# Sensor.net
KiCad netlist of a schematic drawn in Altium Designer
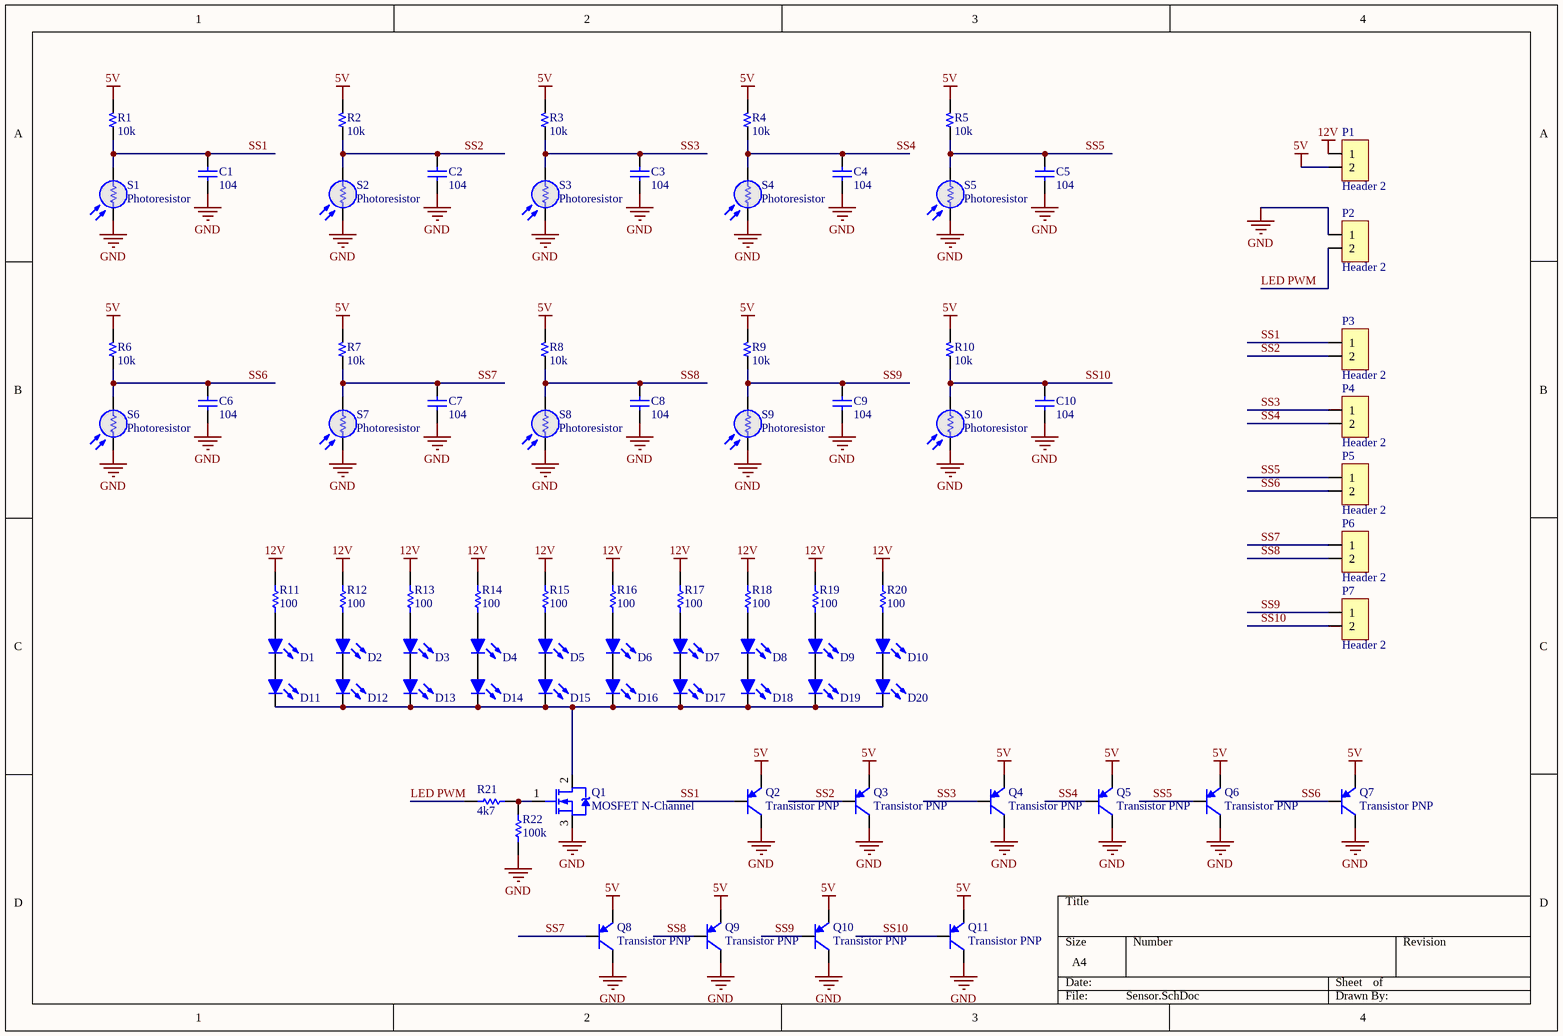
[diagram p0: Sensor.SchDoc]

(export (version "E")
  (design (tool "Eeschema 10.0.6"))
  (components
    (comp (ref "C1")
      (value "104")
      (footprint "C 0805")
      (description "Capacitor non-pol")
      (libsource (lib "chipfc_altium_libs") (part "Capacitor NP"))
    )
    (comp (ref "C2")
      (value "104")
      (footprint "C 0805")
      (description "Capacitor non-pol")
      (libsource (lib "chipfc_altium_libs") (part "Capacitor NP"))
    )
    (comp (ref "C3")
      (value "104")
      (footprint "C 0805")
      (description "Capacitor non-pol")
      (libsource (lib "chipfc_altium_libs") (part "Capacitor NP"))
    )
    (comp (ref "C4")
      (value "104")
      (footprint "C 0805")
      (description "Capacitor non-pol")
      (libsource (lib "chipfc_altium_libs") (part "Capacitor NP"))
    )
    (comp (ref "C5")
      (value "104")
      (footprint "C 0805")
      (description "Capacitor non-pol")
      (libsource (lib "chipfc_altium_libs") (part "Capacitor NP"))
    )
    (comp (ref "C6")
      (value "104")
      (footprint "C 0805")
      (description "Capacitor non-pol")
      (libsource (lib "chipfc_altium_libs") (part "Capacitor NP"))
    )
    (comp (ref "C7")
      (value "104")
      (footprint "C 0805")
      (description "Capacitor non-pol")
      (libsource (lib "chipfc_altium_libs") (part "Capacitor NP"))
    )
    (comp (ref "C8")
      (value "104")
      (footprint "C 0805")
      (description "Capacitor non-pol")
      (libsource (lib "chipfc_altium_libs") (part "Capacitor NP"))
    )
    (comp (ref "C9")
      (value "104")
      (footprint "C 0805")
      (description "Capacitor non-pol")
      (libsource (lib "chipfc_altium_libs") (part "Capacitor NP"))
    )
    (comp (ref "C10")
      (value "104")
      (footprint "C 0805")
      (description "Capacitor non-pol")
      (libsource (lib "chipfc_altium_libs") (part "Capacitor NP"))
    )
    (comp (ref "D1")
      (value "Led")
      (footprint "LED 5MM - WHITE")
      (description "Typical LED")
      (libsource (lib "chipfc_altium_libs") (part "Led"))
    )
    (comp (ref "D2")
      (value "Led")
      (footprint "LED 5MM - WHITE")
      (description "Typical LED")
      (libsource (lib "chipfc_altium_libs") (part "Led"))
    )
    (comp (ref "D3")
      (value "Led")
      (footprint "LED 5MM - WHITE")
      (description "Typical LED")
      (libsource (lib "chipfc_altium_libs") (part "Led"))
    )
    (comp (ref "D4")
      (value "Led")
      (footprint "LED 5MM - WHITE")
      (description "Typical LED")
      (libsource (lib "chipfc_altium_libs") (part "Led"))
    )
    (comp (ref "D5")
      (value "Led")
      (footprint "LED 5MM - WHITE")
      (description "Typical LED")
      (libsource (lib "chipfc_altium_libs") (part "Led"))
    )
    (comp (ref "D6")
      (value "Led")
      (footprint "LED 5MM - WHITE")
      (description "Typical LED")
      (libsource (lib "chipfc_altium_libs") (part "Led"))
    )
    (comp (ref "D7")
      (value "Led")
      (footprint "LED 5MM - WHITE")
      (description "Typical LED")
      (libsource (lib "chipfc_altium_libs") (part "Led"))
    )
    (comp (ref "D8")
      (value "Led")
      (footprint "LED 5MM - WHITE")
      (description "Typical LED")
      (libsource (lib "chipfc_altium_libs") (part "Led"))
    )
    (comp (ref "D9")
      (value "Led")
      (footprint "LED 5MM - WHITE")
      (description "Typical LED")
      (libsource (lib "chipfc_altium_libs") (part "Led"))
    )
    (comp (ref "D10")
      (value "Led")
      (footprint "LED 5MM - WHITE")
      (description "Typical LED")
      (libsource (lib "chipfc_altium_libs") (part "Led"))
    )
    (comp (ref "D11")
      (value "Led")
      (footprint "LED 5MM - WHITE")
      (description "Typical LED")
      (libsource (lib "chipfc_altium_libs") (part "Led"))
    )
    (comp (ref "D12")
      (value "Led")
      (footprint "LED 5MM - WHITE")
      (description "Typical LED")
      (libsource (lib "chipfc_altium_libs") (part "Led"))
    )
    (comp (ref "D13")
      (value "Led")
      (footprint "LED 5MM - WHITE")
      (description "Typical LED")
      (libsource (lib "chipfc_altium_libs") (part "Led"))
    )
    (comp (ref "D14")
      (value "Led")
      (footprint "LED 5MM - WHITE")
      (description "Typical LED")
      (libsource (lib "chipfc_altium_libs") (part "Led"))
    )
    (comp (ref "D15")
      (value "Led")
      (footprint "LED 5MM - WHITE")
      (description "Typical LED")
      (libsource (lib "chipfc_altium_libs") (part "Led"))
    )
    (comp (ref "D16")
      (value "Led")
      (footprint "LED 5MM - WHITE")
      (description "Typical LED")
      (libsource (lib "chipfc_altium_libs") (part "Led"))
    )
    (comp (ref "D17")
      (value "Led")
      (footprint "LED 5MM - WHITE")
      (description "Typical LED")
      (libsource (lib "chipfc_altium_libs") (part "Led"))
    )
    (comp (ref "D18")
      (value "Led")
      (footprint "LED 5MM - WHITE")
      (description "Typical LED")
      (libsource (lib "chipfc_altium_libs") (part "Led"))
    )
    (comp (ref "D19")
      (value "Led")
      (footprint "LED 5MM - WHITE")
      (description "Typical LED")
      (libsource (lib "chipfc_altium_libs") (part "Led"))
    )
    (comp (ref "D20")
      (value "Led")
      (footprint "LED 5MM - WHITE")
      (description "Typical LED")
      (libsource (lib "chipfc_altium_libs") (part "Led"))
    )
    (comp (ref "P1")
      (value "Header 2")
      (footprint "HDR Domino 2 - 5MM")
      (description "Header, 2-Pin")
      (fields (field (name "PUBLISHER") "Altium Limited"))
      (libsource (lib "BKIT4U_LIB") (part "Header 2"))
    )
    (comp (ref "P2")
      (value "Header 2")
      (footprint "HDR Domino 2 - 5MM")
      (description "Header, 2-Pin")
      (fields (field (name "PUBLISHER") "Altium Limited"))
      (libsource (lib "BKIT4U_LIB") (part "Header 2"))
    )
    (comp (ref "P3")
      (value "Header 2")
      (footprint "HDR Domino 2 - 5MM")
      (description "Header, 2-Pin")
      (fields (field (name "PUBLISHER") "Altium Limited"))
      (libsource (lib "BKIT4U_LIB") (part "Header 2"))
    )
    (comp (ref "P4")
      (value "Header 2")
      (footprint "HDR Domino 2 - 5MM")
      (description "Header, 2-Pin")
      (fields (field (name "PUBLISHER") "Altium Limited"))
      (libsource (lib "BKIT4U_LIB") (part "Header 2"))
    )
    (comp (ref "P5")
      (value "Header 2")
      (footprint "HDR Domino 2 - 5MM")
      (description "Header, 2-Pin")
      (fields (field (name "PUBLISHER") "Altium Limited"))
      (libsource (lib "BKIT4U_LIB") (part "Header 2"))
    )
    (comp (ref "P6")
      (value "Header 2")
      (footprint "HDR Domino 2 - 5MM")
      (description "Header, 2-Pin")
      (fields (field (name "PUBLISHER") "Altium Limited"))
      (libsource (lib "BKIT4U_LIB") (part "Header 2"))
    )
    (comp (ref "P7")
      (value "Header 2")
      (footprint "HDR Domino 2 - 5MM")
      (description "Header, 2-Pin")
      (fields (field (name "PUBLISHER") "Altium Limited"))
      (libsource (lib "BKIT4U_LIB") (part "Header 2"))
    )
    (comp (ref "Q1")
      (value "MOSFET N-Channel")
      (footprint "TO-252 (DPAK)")
      (libsource (lib "BKIT4U_LIB") (part "MOSFET N-Channel"))
    )
    (comp (ref "Q2")
      (value "Transistor PNP")
      (footprint "TO-92")
      (description "PNP Bipolar Transistor")
      (libsource (lib "chipfc_altium_libs") (part "Transistor PNP"))
    )
    (comp (ref "Q3")
      (value "Transistor PNP")
      (footprint "TO-92")
      (description "PNP Bipolar Transistor")
      (libsource (lib "chipfc_altium_libs") (part "Transistor PNP"))
    )
    (comp (ref "Q4")
      (value "Transistor PNP")
      (footprint "TO-92")
      (description "PNP Bipolar Transistor")
      (libsource (lib "chipfc_altium_libs") (part "Transistor PNP"))
    )
    (comp (ref "Q5")
      (value "Transistor PNP")
      (footprint "TO-92")
      (description "PNP Bipolar Transistor")
      (libsource (lib "chipfc_altium_libs") (part "Transistor PNP"))
    )
    (comp (ref "Q6")
      (value "Transistor PNP")
      (footprint "TO-92")
      (description "PNP Bipolar Transistor")
      (libsource (lib "chipfc_altium_libs") (part "Transistor PNP"))
    )
    (comp (ref "Q7")
      (value "Transistor PNP")
      (footprint "TO-92")
      (description "PNP Bipolar Transistor")
      (libsource (lib "chipfc_altium_libs") (part "Transistor PNP"))
    )
    (comp (ref "Q8")
      (value "Transistor PNP")
      (footprint "TO-92")
      (description "PNP Bipolar Transistor")
      (libsource (lib "chipfc_altium_libs") (part "Transistor PNP"))
    )
    (comp (ref "Q9")
      (value "Transistor PNP")
      (footprint "TO-92")
      (description "PNP Bipolar Transistor")
      (libsource (lib "chipfc_altium_libs") (part "Transistor PNP"))
    )
    (comp (ref "Q10")
      (value "Transistor PNP")
      (footprint "TO-92")
      (description "PNP Bipolar Transistor")
      (libsource (lib "chipfc_altium_libs") (part "Transistor PNP"))
    )
    (comp (ref "Q11")
      (value "Transistor PNP")
      (footprint "TO-92")
      (description "PNP Bipolar Transistor")
      (libsource (lib "chipfc_altium_libs") (part "Transistor PNP"))
    )
    (comp (ref "R1")
      (value "10k")
      (footprint "R 0805")
      (description "Resistor")
      (libsource (lib "chipfc_altium_libs") (part "Resistor"))
    )
    (comp (ref "R2")
      (value "10k")
      (footprint "R 0805")
      (description "Resistor")
      (libsource (lib "chipfc_altium_libs") (part "Resistor"))
    )
    (comp (ref "R3")
      (value "10k")
      (footprint "R 0805")
      (description "Resistor")
      (libsource (lib "chipfc_altium_libs") (part "Resistor"))
    )
    (comp (ref "R4")
      (value "10k")
      (footprint "R 0805")
      (description "Resistor")
      (libsource (lib "chipfc_altium_libs") (part "Resistor"))
    )
    (comp (ref "R5")
      (value "10k")
      (footprint "R 0805")
      (description "Resistor")
      (libsource (lib "chipfc_altium_libs") (part "Resistor"))
    )
    (comp (ref "R6")
      (value "10k")
      (footprint "R 0805")
      (description "Resistor")
      (libsource (lib "chipfc_altium_libs") (part "Resistor"))
    )
    (comp (ref "R7")
      (value "10k")
      (footprint "R 0805")
      (description "Resistor")
      (libsource (lib "chipfc_altium_libs") (part "Resistor"))
    )
    (comp (ref "R8")
      (value "10k")
      (footprint "R 0805")
      (description "Resistor")
      (libsource (lib "chipfc_altium_libs") (part "Resistor"))
    )
    (comp (ref "R9")
      (value "10k")
      (footprint "R 0805")
      (description "Resistor")
      (libsource (lib "chipfc_altium_libs") (part "Resistor"))
    )
    (comp (ref "R10")
      (value "10k")
      (footprint "R 0805")
      (description "Resistor")
      (libsource (lib "chipfc_altium_libs") (part "Resistor"))
    )
    (comp (ref "R11")
      (value "100")
      (footprint "R 0805 (2012)")
      (description "Resistor")
      (fields (field (name "PUBLISHER") "Altium Limited"))
      (libsource (lib "BKIT4U_LIB") (part "Resistor"))
    )
    (comp (ref "R12")
      (value "100")
      (footprint "R 0805 (2012)")
      (description "Resistor")
      (fields (field (name "PUBLISHER") "Altium Limited"))
      (libsource (lib "BKIT4U_LIB") (part "Resistor"))
    )
    (comp (ref "R13")
      (value "100")
      (footprint "R 0805 (2012)")
      (description "Resistor")
      (fields (field (name "PUBLISHER") "Altium Limited"))
      (libsource (lib "BKIT4U_LIB") (part "Resistor"))
    )
    (comp (ref "R14")
      (value "100")
      (footprint "R 0805 (2012)")
      (description "Resistor")
      (fields (field (name "PUBLISHER") "Altium Limited"))
      (libsource (lib "BKIT4U_LIB") (part "Resistor"))
    )
    (comp (ref "R15")
      (value "100")
      (footprint "R 0805 (2012)")
      (description "Resistor")
      (fields (field (name "PUBLISHER") "Altium Limited"))
      (libsource (lib "BKIT4U_LIB") (part "Resistor"))
    )
    (comp (ref "R16")
      (value "100")
      (footprint "R 0805 (2012)")
      (description "Resistor")
      (fields (field (name "PUBLISHER") "Altium Limited"))
      (libsource (lib "BKIT4U_LIB") (part "Resistor"))
    )
    (comp (ref "R17")
      (value "100")
      (footprint "R 0805 (2012)")
      (description "Resistor")
      (fields (field (name "PUBLISHER") "Altium Limited"))
      (libsource (lib "BKIT4U_LIB") (part "Resistor"))
    )
    (comp (ref "R18")
      (value "100")
      (footprint "R 0805 (2012)")
      (description "Resistor")
      (fields (field (name "PUBLISHER") "Altium Limited"))
      (libsource (lib "BKIT4U_LIB") (part "Resistor"))
    )
    (comp (ref "R19")
      (value "100")
      (footprint "R 0805 (2012)")
      (description "Resistor")
      (fields (field (name "PUBLISHER") "Altium Limited"))
      (libsource (lib "BKIT4U_LIB") (part "Resistor"))
    )
    (comp (ref "R20")
      (value "100")
      (footprint "R 0805 (2012)")
      (description "Resistor")
      (fields (field (name "PUBLISHER") "Altium Limited"))
      (libsource (lib "BKIT4U_LIB") (part "Resistor"))
    )
    (comp (ref "R21")
      (value "4k7")
      (footprint "R 0805 (2012)")
      (description "Resistor")
      (fields (field (name "PUBLISHER") "Altium Limited"))
      (libsource (lib "BKIT4U_LIB") (part "Resistor"))
    )
    (comp (ref "R22")
      (value "100k")
      (footprint "R 0805 (2012)")
      (description "Resistor")
      (fields (field (name "PUBLISHER") "Altium Limited"))
      (libsource (lib "BKIT4U_LIB") (part "Resistor"))
    )
    (comp (ref "S1")
      (value "Photoresistor")
      (footprint "PHOTOCELL/12mm")
      (description "Light dependent resistors")
      (libsource (lib "chipfc_altium_libs") (part "Photoresistor"))
    )
    (comp (ref "S2")
      (value "Photoresistor")
      (footprint "PHOTOCELL/12mm")
      (description "Light dependent resistors")
      (libsource (lib "chipfc_altium_libs") (part "Photoresistor"))
    )
    (comp (ref "S3")
      (value "Photoresistor")
      (footprint "PHOTOCELL/12mm")
      (description "Light dependent resistors")
      (libsource (lib "chipfc_altium_libs") (part "Photoresistor"))
    )
    (comp (ref "S4")
      (value "Photoresistor")
      (footprint "PHOTOCELL/12mm")
      (description "Light dependent resistors")
      (libsource (lib "chipfc_altium_libs") (part "Photoresistor"))
    )
    (comp (ref "S5")
      (value "Photoresistor")
      (footprint "PHOTOCELL/12mm")
      (description "Light dependent resistors")
      (libsource (lib "chipfc_altium_libs") (part "Photoresistor"))
    )
    (comp (ref "S6")
      (value "Photoresistor")
      (footprint "PHOTOCELL/12mm")
      (description "Light dependent resistors")
      (libsource (lib "chipfc_altium_libs") (part "Photoresistor"))
    )
    (comp (ref "S7")
      (value "Photoresistor")
      (footprint "PHOTOCELL/12mm")
      (description "Light dependent resistors")
      (libsource (lib "chipfc_altium_libs") (part "Photoresistor"))
    )
    (comp (ref "S8")
      (value "Photoresistor")
      (footprint "PHOTOCELL/12mm")
      (description "Light dependent resistors")
      (libsource (lib "chipfc_altium_libs") (part "Photoresistor"))
    )
    (comp (ref "S9")
      (value "Photoresistor")
      (footprint "PHOTOCELL/12mm")
      (description "Light dependent resistors")
      (libsource (lib "chipfc_altium_libs") (part "Photoresistor"))
    )
    (comp (ref "S10")
      (value "Photoresistor")
      (footprint "PHOTOCELL/12mm")
      (description "Light dependent resistors")
      (libsource (lib "chipfc_altium_libs") (part "Photoresistor"))
    )
  )
  (nets
    (net (code "1") (name "/LED PWM") (class "Default")
      (node (ref "P2") (pin "2") (pinfunction "2_2") (pintype "passive"))
      (node (ref "R21") (pin "2") (pinfunction "2_2") (pintype "passive"))
    )
    (net (code "2") (name "/SS1") (class "Default")
      (node (ref "C1") (pin "1") (pinfunction "1_1") (pintype "passive"))
      (node (ref "P3") (pin "1") (pinfunction "1_1") (pintype "passive"))
      (node (ref "Q2") (pin "1") (pinfunction "B_1") (pintype "passive"))
      (node (ref "R1") (pin "1") (pinfunction "1_1") (pintype "passive"))
      (node (ref "S1") (pin "2") (pinfunction "2_2") (pintype "passive"))
    )
    (net (code "3") (name "/SS2") (class "Default")
      (node (ref "C2") (pin "1") (pinfunction "1_1") (pintype "passive"))
      (node (ref "P3") (pin "2") (pinfunction "2_2") (pintype "passive"))
      (node (ref "Q3") (pin "1") (pinfunction "B_1") (pintype "passive"))
      (node (ref "R2") (pin "1") (pinfunction "1_1") (pintype "passive"))
      (node (ref "S2") (pin "2") (pinfunction "2_2") (pintype "passive"))
    )
    (net (code "4") (name "/SS3") (class "Default")
      (node (ref "C3") (pin "1") (pinfunction "1_1") (pintype "passive"))
      (node (ref "P4") (pin "1") (pinfunction "1_1") (pintype "passive"))
      (node (ref "Q4") (pin "1") (pinfunction "B_1") (pintype "passive"))
      (node (ref "R3") (pin "1") (pinfunction "1_1") (pintype "passive"))
      (node (ref "S3") (pin "2") (pinfunction "2_2") (pintype "passive"))
    )
    (net (code "5") (name "/SS4") (class "Default")
      (node (ref "C4") (pin "1") (pinfunction "1_1") (pintype "passive"))
      (node (ref "P4") (pin "2") (pinfunction "2_2") (pintype "passive"))
      (node (ref "Q5") (pin "1") (pinfunction "B_1") (pintype "passive"))
      (node (ref "R4") (pin "1") (pinfunction "1_1") (pintype "passive"))
      (node (ref "S4") (pin "2") (pinfunction "2_2") (pintype "passive"))
    )
    (net (code "6") (name "/SS5") (class "Default")
      (node (ref "C5") (pin "1") (pinfunction "1_1") (pintype "passive"))
      (node (ref "P5") (pin "1") (pinfunction "1_1") (pintype "passive"))
      (node (ref "Q6") (pin "1") (pinfunction "B_1") (pintype "passive"))
      (node (ref "R5") (pin "1") (pinfunction "1_1") (pintype "passive"))
      (node (ref "S5") (pin "2") (pinfunction "2_2") (pintype "passive"))
    )
    (net (code "7") (name "/SS6") (class "Default")
      (node (ref "C6") (pin "1") (pinfunction "1_1") (pintype "passive"))
      (node (ref "P5") (pin "2") (pinfunction "2_2") (pintype "passive"))
      (node (ref "Q7") (pin "1") (pinfunction "B_1") (pintype "passive"))
      (node (ref "R6") (pin "1") (pinfunction "1_1") (pintype "passive"))
      (node (ref "S6") (pin "2") (pinfunction "2_2") (pintype "passive"))
    )
    (net (code "8") (name "/SS7") (class "Default")
      (node (ref "C7") (pin "1") (pinfunction "1_1") (pintype "passive"))
      (node (ref "P6") (pin "1") (pinfunction "1_1") (pintype "passive"))
      (node (ref "Q8") (pin "1") (pinfunction "B_1") (pintype "passive"))
      (node (ref "R7") (pin "1") (pinfunction "1_1") (pintype "passive"))
      (node (ref "S7") (pin "2") (pinfunction "2_2") (pintype "passive"))
    )
    (net (code "9") (name "/SS8") (class "Default")
      (node (ref "C8") (pin "1") (pinfunction "1_1") (pintype "passive"))
      (node (ref "P6") (pin "2") (pinfunction "2_2") (pintype "passive"))
      (node (ref "Q9") (pin "1") (pinfunction "B_1") (pintype "passive"))
      (node (ref "R8") (pin "1") (pinfunction "1_1") (pintype "passive"))
      (node (ref "S8") (pin "2") (pinfunction "2_2") (pintype "passive"))
    )
    (net (code "10") (name "/SS9") (class "Default")
      (node (ref "C9") (pin "1") (pinfunction "1_1") (pintype "passive"))
      (node (ref "P7") (pin "1") (pinfunction "1_1") (pintype "passive"))
      (node (ref "Q10") (pin "1") (pinfunction "B_1") (pintype "passive"))
      (node (ref "R9") (pin "1") (pinfunction "1_1") (pintype "passive"))
      (node (ref "S9") (pin "2") (pinfunction "2_2") (pintype "passive"))
    )
    (net (code "11") (name "/SS10") (class "Default")
      (node (ref "C10") (pin "1") (pinfunction "1_1") (pintype "passive"))
      (node (ref "P7") (pin "2") (pinfunction "2_2") (pintype "passive"))
      (node (ref "Q11") (pin "1") (pinfunction "B_1") (pintype "passive"))
      (node (ref "R10") (pin "1") (pinfunction "1_1") (pintype "passive"))
      (node (ref "S10") (pin "2") (pinfunction "2_2") (pintype "passive"))
    )
    (net (code "12") (name "5V") (class "Default")
      (node (ref "P1") (pin "2") (pinfunction "2_2") (pintype "passive"))
      (node (ref "Q10") (pin "2") (pinfunction "E_2") (pintype "passive"))
      (node (ref "Q11") (pin "2") (pinfunction "E_2") (pintype "passive"))
      (node (ref "Q2") (pin "2") (pinfunction "E_2") (pintype "passive"))
      (node (ref "Q3") (pin "2") (pinfunction "E_2") (pintype "passive"))
      (node (ref "Q4") (pin "2") (pinfunction "E_2") (pintype "passive"))
      (node (ref "Q5") (pin "2") (pinfunction "E_2") (pintype "passive"))
      (node (ref "Q6") (pin "2") (pinfunction "E_2") (pintype "passive"))
      (node (ref "Q7") (pin "2") (pinfunction "E_2") (pintype "passive"))
      (node (ref "Q8") (pin "2") (pinfunction "E_2") (pintype "passive"))
      (node (ref "Q9") (pin "2") (pinfunction "E_2") (pintype "passive"))
      (node (ref "R1") (pin "2") (pinfunction "2_2") (pintype "passive"))
      (node (ref "R10") (pin "2") (pinfunction "2_2") (pintype "passive"))
      (node (ref "R2") (pin "2") (pinfunction "2_2") (pintype "passive"))
      (node (ref "R3") (pin "2") (pinfunction "2_2") (pintype "passive"))
      (node (ref "R4") (pin "2") (pinfunction "2_2") (pintype "passive"))
      (node (ref "R5") (pin "2") (pinfunction "2_2") (pintype "passive"))
      (node (ref "R6") (pin "2") (pinfunction "2_2") (pintype "passive"))
      (node (ref "R7") (pin "2") (pinfunction "2_2") (pintype "passive"))
      (node (ref "R8") (pin "2") (pinfunction "2_2") (pintype "passive"))
      (node (ref "R9") (pin "2") (pinfunction "2_2") (pintype "passive"))
    )
    (net (code "13") (name "12V") (class "Default")
      (node (ref "P1") (pin "1") (pinfunction "1_1") (pintype "passive"))
      (node (ref "R11") (pin "2") (pinfunction "2_2") (pintype "passive"))
      (node (ref "R12") (pin "2") (pinfunction "2_2") (pintype "passive"))
      (node (ref "R13") (pin "2") (pinfunction "2_2") (pintype "passive"))
      (node (ref "R14") (pin "2") (pinfunction "2_2") (pintype "passive"))
      (node (ref "R15") (pin "2") (pinfunction "2_2") (pintype "passive"))
      (node (ref "R16") (pin "2") (pinfunction "2_2") (pintype "passive"))
      (node (ref "R17") (pin "2") (pinfunction "2_2") (pintype "passive"))
      (node (ref "R18") (pin "2") (pinfunction "2_2") (pintype "passive"))
      (node (ref "R19") (pin "2") (pinfunction "2_2") (pintype "passive"))
      (node (ref "R20") (pin "2") (pinfunction "2_2") (pintype "passive"))
    )
    (net (code "14") (name "GND") (class "Default")
      (node (ref "C1") (pin "2") (pinfunction "2_2") (pintype "passive"))
      (node (ref "C10") (pin "2") (pinfunction "2_2") (pintype "passive"))
      (node (ref "C2") (pin "2") (pinfunction "2_2") (pintype "passive"))
      (node (ref "C3") (pin "2") (pinfunction "2_2") (pintype "passive"))
      (node (ref "C4") (pin "2") (pinfunction "2_2") (pintype "passive"))
      (node (ref "C5") (pin "2") (pinfunction "2_2") (pintype "passive"))
      (node (ref "C6") (pin "2") (pinfunction "2_2") (pintype "passive"))
      (node (ref "C7") (pin "2") (pinfunction "2_2") (pintype "passive"))
      (node (ref "C8") (pin "2") (pinfunction "2_2") (pintype "passive"))
      (node (ref "C9") (pin "2") (pinfunction "2_2") (pintype "passive"))
      (node (ref "P2") (pin "1") (pinfunction "1_1") (pintype "passive"))
      (node (ref "Q1") (pin "3") (pinfunction "S_3") (pintype "passive"))
      (node (ref "Q10") (pin "3") (pinfunction "C_3") (pintype "passive"))
      (node (ref "Q11") (pin "3") (pinfunction "C_3") (pintype "passive"))
      (node (ref "Q2") (pin "3") (pinfunction "C_3") (pintype "passive"))
      (node (ref "Q3") (pin "3") (pinfunction "C_3") (pintype "passive"))
      (node (ref "Q4") (pin "3") (pinfunction "C_3") (pintype "passive"))
      (node (ref "Q5") (pin "3") (pinfunction "C_3") (pintype "passive"))
      (node (ref "Q6") (pin "3") (pinfunction "C_3") (pintype "passive"))
      (node (ref "Q7") (pin "3") (pinfunction "C_3") (pintype "passive"))
      (node (ref "Q8") (pin "3") (pinfunction "C_3") (pintype "passive"))
      (node (ref "Q9") (pin "3") (pinfunction "C_3") (pintype "passive"))
      (node (ref "R22") (pin "1") (pinfunction "1_1") (pintype "passive"))
      (node (ref "S1") (pin "1") (pinfunction "1_1") (pintype "passive"))
      (node (ref "S10") (pin "1") (pinfunction "1_1") (pintype "passive"))
      (node (ref "S2") (pin "1") (pinfunction "1_1") (pintype "passive"))
      (node (ref "S3") (pin "1") (pinfunction "1_1") (pintype "passive"))
      (node (ref "S4") (pin "1") (pinfunction "1_1") (pintype "passive"))
      (node (ref "S5") (pin "1") (pinfunction "1_1") (pintype "passive"))
      (node (ref "S6") (pin "1") (pinfunction "1_1") (pintype "passive"))
      (node (ref "S7") (pin "1") (pinfunction "1_1") (pintype "passive"))
      (node (ref "S8") (pin "1") (pinfunction "1_1") (pintype "passive"))
      (node (ref "S9") (pin "1") (pinfunction "1_1") (pintype "passive"))
    )
    (net (code "15") (name "Net-(D1-A)") (class "Default")
      (node (ref "D1") (pin "1") (pinfunction "A_1") (pintype "passive"))
      (node (ref "R11") (pin "1") (pinfunction "1_1") (pintype "passive"))
    )
    (net (code "16") (name "Net-(D1-K)") (class "Default")
      (node (ref "D1") (pin "2") (pinfunction "K_2") (pintype "passive"))
      (node (ref "D11") (pin "1") (pinfunction "A_1") (pintype "passive"))
    )
    (net (code "17") (name "Net-(D2-A)") (class "Default")
      (node (ref "D2") (pin "1") (pinfunction "A_1") (pintype "passive"))
      (node (ref "R12") (pin "1") (pinfunction "1_1") (pintype "passive"))
    )
    (net (code "18") (name "Net-(D3-A)") (class "Default")
      (node (ref "D3") (pin "1") (pinfunction "A_1") (pintype "passive"))
      (node (ref "R13") (pin "1") (pinfunction "1_1") (pintype "passive"))
    )
    (net (code "19") (name "Net-(D4-A)") (class "Default")
      (node (ref "D4") (pin "1") (pinfunction "A_1") (pintype "passive"))
      (node (ref "R14") (pin "1") (pinfunction "1_1") (pintype "passive"))
    )
    (net (code "20") (name "Net-(D5-A)") (class "Default")
      (node (ref "D5") (pin "1") (pinfunction "A_1") (pintype "passive"))
      (node (ref "R15") (pin "1") (pinfunction "1_1") (pintype "passive"))
    )
    (net (code "21") (name "Net-(D6-A)") (class "Default")
      (node (ref "D6") (pin "1") (pinfunction "A_1") (pintype "passive"))
      (node (ref "R16") (pin "1") (pinfunction "1_1") (pintype "passive"))
    )
    (net (code "22") (name "Net-(D7-A)") (class "Default")
      (node (ref "D7") (pin "1") (pinfunction "A_1") (pintype "passive"))
      (node (ref "R17") (pin "1") (pinfunction "1_1") (pintype "passive"))
    )
    (net (code "23") (name "Net-(D8-A)") (class "Default")
      (node (ref "D8") (pin "1") (pinfunction "A_1") (pintype "passive"))
      (node (ref "R18") (pin "1") (pinfunction "1_1") (pintype "passive"))
    )
    (net (code "24") (name "Net-(D9-A)") (class "Default")
      (node (ref "D9") (pin "1") (pinfunction "A_1") (pintype "passive"))
      (node (ref "R19") (pin "1") (pinfunction "1_1") (pintype "passive"))
    )
    (net (code "25") (name "Net-(D10-A)") (class "Default")
      (node (ref "D10") (pin "1") (pinfunction "A_1") (pintype "passive"))
      (node (ref "R20") (pin "1") (pinfunction "1_1") (pintype "passive"))
    )
    (net (code "26") (name "Net-(D10-K)") (class "Default")
      (node (ref "D10") (pin "2") (pinfunction "K_2") (pintype "passive"))
      (node (ref "D20") (pin "1") (pinfunction "A_1") (pintype "passive"))
    )
    (net (code "27") (name "Net-(D11-K)") (class "Default")
      (node (ref "D11") (pin "2") (pinfunction "K_2") (pintype "passive"))
      (node (ref "D12") (pin "2") (pinfunction "K_2") (pintype "passive"))
      (node (ref "D13") (pin "2") (pinfunction "K_2") (pintype "passive"))
      (node (ref "D14") (pin "2") (pinfunction "K_2") (pintype "passive"))
      (node (ref "D15") (pin "2") (pinfunction "K_2") (pintype "passive"))
      (node (ref "D16") (pin "2") (pinfunction "K_2") (pintype "passive"))
      (node (ref "D17") (pin "2") (pinfunction "K_2") (pintype "passive"))
      (node (ref "D18") (pin "2") (pinfunction "K_2") (pintype "passive"))
      (node (ref "D19") (pin "2") (pinfunction "K_2") (pintype "passive"))
      (node (ref "D20") (pin "2") (pinfunction "K_2") (pintype "passive"))
      (node (ref "Q1") (pin "2") (pinfunction "D_2") (pintype "passive"))
    )
    (net (code "28") (name "Net-(D12-A)") (class "Default")
      (node (ref "D12") (pin "1") (pinfunction "A_1") (pintype "passive"))
      (node (ref "D2") (pin "2") (pinfunction "K_2") (pintype "passive"))
    )
    (net (code "29") (name "Net-(D13-A)") (class "Default")
      (node (ref "D13") (pin "1") (pinfunction "A_1") (pintype "passive"))
      (node (ref "D3") (pin "2") (pinfunction "K_2") (pintype "passive"))
    )
    (net (code "30") (name "Net-(D14-A)") (class "Default")
      (node (ref "D14") (pin "1") (pinfunction "A_1") (pintype "passive"))
      (node (ref "D4") (pin "2") (pinfunction "K_2") (pintype "passive"))
    )
    (net (code "31") (name "Net-(D15-A)") (class "Default")
      (node (ref "D15") (pin "1") (pinfunction "A_1") (pintype "passive"))
      (node (ref "D5") (pin "2") (pinfunction "K_2") (pintype "passive"))
    )
    (net (code "32") (name "Net-(D16-A)") (class "Default")
      (node (ref "D16") (pin "1") (pinfunction "A_1") (pintype "passive"))
      (node (ref "D6") (pin "2") (pinfunction "K_2") (pintype "passive"))
    )
    (net (code "33") (name "Net-(D17-A)") (class "Default")
      (node (ref "D17") (pin "1") (pinfunction "A_1") (pintype "passive"))
      (node (ref "D7") (pin "2") (pinfunction "K_2") (pintype "passive"))
    )
    (net (code "34") (name "Net-(D18-A)") (class "Default")
      (node (ref "D18") (pin "1") (pinfunction "A_1") (pintype "passive"))
      (node (ref "D8") (pin "2") (pinfunction "K_2") (pintype "passive"))
    )
    (net (code "35") (name "Net-(D19-A)") (class "Default")
      (node (ref "D19") (pin "1") (pinfunction "A_1") (pintype "passive"))
      (node (ref "D9") (pin "2") (pinfunction "K_2") (pintype "passive"))
    )
    (net (code "36") (name "Net-(Q1-G)") (class "Default")
      (node (ref "Q1") (pin "1") (pinfunction "G_1") (pintype "passive"))
      (node (ref "R21") (pin "1") (pinfunction "1_1") (pintype "passive"))
      (node (ref "R22") (pin "2") (pinfunction "2_2") (pintype "passive"))
    )
  )
)
